# controller-2.net
KiCad netlist of a schematic drawn in EAGLE
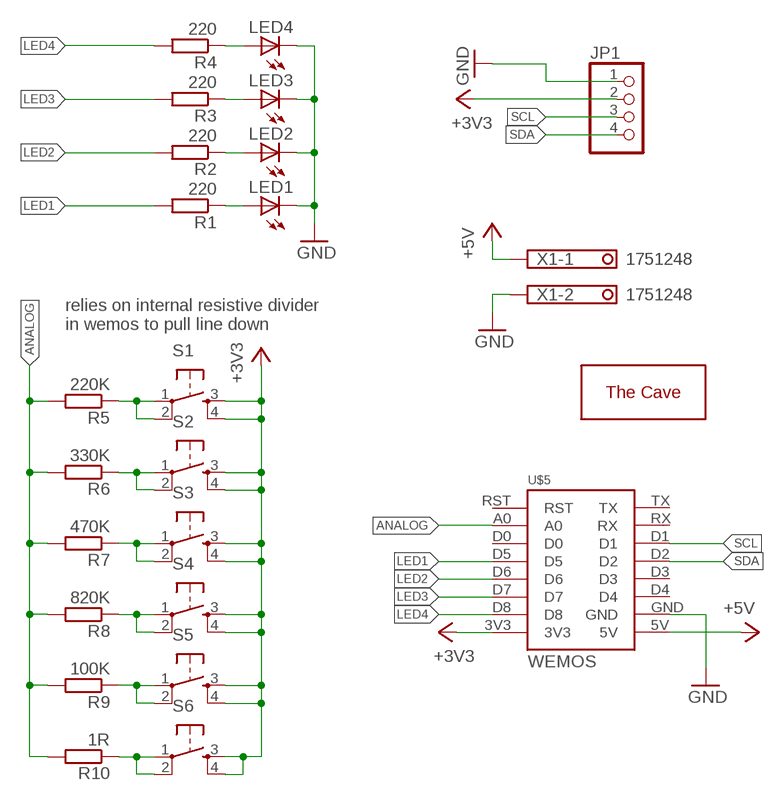
[diagram p0: schematic, sheet 1]

(export (version "E")
  (design (tool "Eeschema 10.0.6"))
  (components
    (comp (ref "JP1")
      (value "PINHD-1X4")
      (footprint "eagle-import:1X04")
      (libsource (lib "eagle-import") (part "PINHD-1X4"))
    )
    (comp (ref "LED1")
      (value "LED5MM")
      (footprint "eagle-import:LED5MM")
      (libsource (lib "eagle-import") (part "LED5MM"))
    )
    (comp (ref "LED2")
      (value "LED5MM")
      (footprint "eagle-import:LED5MM")
      (libsource (lib "eagle-import") (part "LED5MM"))
    )
    (comp (ref "LED3")
      (value "LED5MM")
      (footprint "eagle-import:LED5MM")
      (libsource (lib "eagle-import") (part "LED5MM"))
    )
    (comp (ref "LED4")
      (value "LED5MM")
      (footprint "eagle-import:LED5MM")
      (libsource (lib "eagle-import") (part "LED5MM"))
    )
    (comp (ref "R1")
      (value "220")
      (footprint "eagle-import:R0805")
      (libsource (lib "eagle-import") (part "R-EU_R0805"))
    )
    (comp (ref "R2")
      (value "220")
      (footprint "eagle-import:R0805")
      (libsource (lib "eagle-import") (part "R-EU_R0805"))
    )
    (comp (ref "R3")
      (value "220")
      (footprint "eagle-import:R0805")
      (libsource (lib "eagle-import") (part "R-EU_R0805"))
    )
    (comp (ref "R4")
      (value "220")
      (footprint "eagle-import:R0805")
      (libsource (lib "eagle-import") (part "R-EU_R0805"))
    )
    (comp (ref "R5")
      (value "220K")
      (footprint "eagle-import:R0805")
      (libsource (lib "eagle-import") (part "R-EU_R0805"))
    )
    (comp (ref "R6")
      (value "330K")
      (footprint "eagle-import:R0805")
      (libsource (lib "eagle-import") (part "R-EU_R0805"))
    )
    (comp (ref "R7")
      (value "470K")
      (footprint "eagle-import:R0805")
      (libsource (lib "eagle-import") (part "R-EU_R0805"))
    )
    (comp (ref "R8")
      (value "820K")
      (footprint "eagle-import:R0805")
      (libsource (lib "eagle-import") (part "R-EU_R0805"))
    )
    (comp (ref "R9")
      (value "100K")
      (footprint "eagle-import:R0805")
      (libsource (lib "eagle-import") (part "R-EU_R0805"))
    )
    (comp (ref "R10")
      (value "1R")
      (footprint "eagle-import:R0805")
      (libsource (lib "eagle-import") (part "R-EU_R0805"))
    )
    (comp (ref "S1")
      (value "TACT-SWITCH-6MM-THT")
      (footprint "eagle-import:TACT-SWITCH-6MM-THT")
      (libsource (lib "eagle-import") (part "TACT-SWITCH-6MM-THT"))
    )
    (comp (ref "S2")
      (value "TACT-SWITCH-6MM-THT")
      (footprint "eagle-import:TACT-SWITCH-6MM-THT")
      (libsource (lib "eagle-import") (part "TACT-SWITCH-6MM-THT"))
    )
    (comp (ref "S3")
      (value "TACT-SWITCH-6MM-THT")
      (footprint "eagle-import:TACT-SWITCH-6MM-THT")
      (libsource (lib "eagle-import") (part "TACT-SWITCH-6MM-THT"))
    )
    (comp (ref "S4")
      (value "TACT-SWITCH-6MM-THT")
      (footprint "eagle-import:TACT-SWITCH-6MM-THT")
      (libsource (lib "eagle-import") (part "TACT-SWITCH-6MM-THT"))
    )
    (comp (ref "S5")
      (value "TACT-SWITCH-6MM-THT")
      (footprint "eagle-import:TACT-SWITCH-6MM-THT")
      (libsource (lib "eagle-import") (part "TACT-SWITCH-6MM-THT"))
    )
    (comp (ref "S6")
      (value "TACT-SWITCH-6MM-THT")
      (footprint "eagle-import:TACT-SWITCH-6MM-THT")
      (libsource (lib "eagle-import") (part "TACT-SWITCH-6MM-THT"))
    )
    (comp (ref "U$1")
      (value "THECAVE_LOGO_NEW_TOP_SMALL")
      (footprint "eagle-import:NEW_LOGO_SMALL_TOP")
      (libsource (lib "eagle-import") (part "THECAVE_LOGO_NEW_TOP_SMALL"))
    )
    (comp (ref "U$5")
      (value "WEMOS")
      (footprint "eagle-import:WEMOS")
      (libsource (lib "eagle-import") (part "WEMOS"))
    )
    (comp (ref "X1")
      (value "1751248")
      (footprint "eagle-import:1751248")
      (libsource (lib "eagle-import") (part "1751248"))
    )
  )
  (nets
    (net (code "1") (name "+3V3") (class "Default")
      (node (ref "JP1") (pin "2") (pinfunction "2_2") (pintype "passive"))
      (node (ref "S1") (pin "3") (pinfunction "3_3") (pintype "passive"))
      (node (ref "S1") (pin "4") (pinfunction "4_4") (pintype "passive"))
      (node (ref "S2") (pin "3") (pinfunction "3_3") (pintype "passive"))
      (node (ref "S2") (pin "4") (pinfunction "4_4") (pintype "passive"))
      (node (ref "S3") (pin "3") (pinfunction "3_3") (pintype "passive"))
      (node (ref "S3") (pin "4") (pinfunction "4_4") (pintype "passive"))
      (node (ref "S4") (pin "3") (pinfunction "3_3") (pintype "passive"))
      (node (ref "S4") (pin "4") (pinfunction "4_4") (pintype "passive"))
      (node (ref "S5") (pin "3") (pinfunction "3_3") (pintype "passive"))
      (node (ref "S5") (pin "4") (pinfunction "4_4") (pintype "passive"))
      (node (ref "S6") (pin "3") (pinfunction "3_3") (pintype "passive"))
      (node (ref "S6") (pin "4") (pinfunction "4_4") (pintype "passive"))
      (node (ref "U$5") (pin "3V3") (pinfunction "3V3_3V3") (pintype "bidirectional"))
    )
    (net (code "2") (name "+5V") (class "Default")
      (node (ref "U$5") (pin "5V") (pinfunction "5V_5V") (pintype "bidirectional"))
      (node (ref "X1") (pin "1") (pinfunction "K_1") (pintype "passive"))
    )
    (net (code "3") (name "ANALOG") (class "Default")
      (node (ref "R10") (pin "2") (pinfunction "2_2") (pintype "passive"))
      (node (ref "R5") (pin "2") (pinfunction "2_2") (pintype "passive"))
      (node (ref "R6") (pin "2") (pinfunction "2_2") (pintype "passive"))
      (node (ref "R7") (pin "2") (pinfunction "2_2") (pintype "passive"))
      (node (ref "R8") (pin "2") (pinfunction "2_2") (pintype "passive"))
      (node (ref "R9") (pin "2") (pinfunction "2_2") (pintype "passive"))
      (node (ref "U$5") (pin "A0") (pinfunction "A0_A0") (pintype "bidirectional"))
    )
    (net (code "4") (name "GND") (class "Default")
      (node (ref "JP1") (pin "1") (pinfunction "1_1") (pintype "passive"))
      (node (ref "LED1") (pin "K") (pinfunction "C_K") (pintype "passive"))
      (node (ref "LED2") (pin "K") (pinfunction "C_K") (pintype "passive"))
      (node (ref "LED3") (pin "K") (pinfunction "C_K") (pintype "passive"))
      (node (ref "LED4") (pin "K") (pinfunction "C_K") (pintype "passive"))
      (node (ref "U$5") (pin "GND") (pinfunction "GND_GND") (pintype "bidirectional"))
      (node (ref "X1") (pin "2") (pinfunction "K_2") (pintype "passive"))
    )
    (net (code "5") (name "LED1") (class "Default")
      (node (ref "R1") (pin "2") (pinfunction "2_2") (pintype "passive"))
      (node (ref "U$5") (pin "D5") (pinfunction "D5_D5") (pintype "bidirectional"))
    )
    (net (code "6") (name "LED2") (class "Default")
      (node (ref "R2") (pin "2") (pinfunction "2_2") (pintype "passive"))
      (node (ref "U$5") (pin "D6") (pinfunction "D6_D6") (pintype "bidirectional"))
    )
    (net (code "7") (name "LED3") (class "Default")
      (node (ref "R3") (pin "2") (pinfunction "2_2") (pintype "passive"))
      (node (ref "U$5") (pin "D7") (pinfunction "D7_D7") (pintype "bidirectional"))
    )
    (net (code "8") (name "LED4") (class "Default")
      (node (ref "R4") (pin "2") (pinfunction "2_2") (pintype "passive"))
      (node (ref "U$5") (pin "D8") (pinfunction "D8_D8") (pintype "bidirectional"))
    )
    (net (code "9") (name "Net-(LED1-PadA)") (class "Default")
      (node (ref "LED1") (pin "A") (pinfunction "A_A") (pintype "passive"))
      (node (ref "R1") (pin "1") (pinfunction "1_1") (pintype "passive"))
    )
    (net (code "10") (name "Net-(LED2-PadA)") (class "Default")
      (node (ref "LED2") (pin "A") (pinfunction "A_A") (pintype "passive"))
      (node (ref "R2") (pin "1") (pinfunction "1_1") (pintype "passive"))
    )
    (net (code "11") (name "Net-(LED3-PadA)") (class "Default")
      (node (ref "LED3") (pin "A") (pinfunction "A_A") (pintype "passive"))
      (node (ref "R3") (pin "1") (pinfunction "1_1") (pintype "passive"))
    )
    (net (code "12") (name "Net-(LED4-PadA)") (class "Default")
      (node (ref "LED4") (pin "A") (pinfunction "A_A") (pintype "passive"))
      (node (ref "R4") (pin "1") (pinfunction "1_1") (pintype "passive"))
    )
    (net (code "13") (name "Net-(R5-Pad1)") (class "Default")
      (node (ref "R5") (pin "1") (pinfunction "1_1") (pintype "passive"))
      (node (ref "S1") (pin "1") (pinfunction "1_1") (pintype "passive"))
      (node (ref "S1") (pin "2") (pinfunction "2_2") (pintype "passive"))
    )
    (net (code "14") (name "Net-(R6-Pad1)") (class "Default")
      (node (ref "R6") (pin "1") (pinfunction "1_1") (pintype "passive"))
      (node (ref "S2") (pin "1") (pinfunction "1_1") (pintype "passive"))
      (node (ref "S2") (pin "2") (pinfunction "2_2") (pintype "passive"))
    )
    (net (code "15") (name "Net-(R7-Pad1)") (class "Default")
      (node (ref "R7") (pin "1") (pinfunction "1_1") (pintype "passive"))
      (node (ref "S3") (pin "1") (pinfunction "1_1") (pintype "passive"))
      (node (ref "S3") (pin "2") (pinfunction "2_2") (pintype "passive"))
    )
    (net (code "16") (name "Net-(R8-Pad1)") (class "Default")
      (node (ref "R8") (pin "1") (pinfunction "1_1") (pintype "passive"))
      (node (ref "S4") (pin "1") (pinfunction "1_1") (pintype "passive"))
      (node (ref "S4") (pin "2") (pinfunction "2_2") (pintype "passive"))
    )
    (net (code "17") (name "Net-(R9-Pad1)") (class "Default")
      (node (ref "R9") (pin "1") (pinfunction "1_1") (pintype "passive"))
      (node (ref "S5") (pin "1") (pinfunction "1_1") (pintype "passive"))
      (node (ref "S5") (pin "2") (pinfunction "2_2") (pintype "passive"))
    )
    (net (code "18") (name "Net-(R10-Pad1)") (class "Default")
      (node (ref "R10") (pin "1") (pinfunction "1_1") (pintype "passive"))
      (node (ref "S6") (pin "1") (pinfunction "1_1") (pintype "passive"))
      (node (ref "S6") (pin "2") (pinfunction "2_2") (pintype "passive"))
    )
    (net (code "19") (name "SCL") (class "Default")
      (node (ref "JP1") (pin "3") (pinfunction "3_3") (pintype "passive"))
      (node (ref "U$5") (pin "D1") (pinfunction "D1_D1") (pintype "bidirectional"))
    )
    (net (code "20") (name "SDA") (class "Default")
      (node (ref "JP1") (pin "4") (pinfunction "4_4") (pintype "passive"))
      (node (ref "U$5") (pin "D2") (pinfunction "D2_D2") (pintype "bidirectional"))
    )
    (net (code "21") (name "unconnected-(U$5-PadD0)") (class "Default")
      (node (ref "U$5") (pin "D0") (pinfunction "D0_D0") (pintype "bidirectional"))
    )
    (net (code "22") (name "unconnected-(U$5-PadD3)") (class "Default")
      (node (ref "U$5") (pin "D3") (pinfunction "D3_D3") (pintype "bidirectional"))
    )
    (net (code "23") (name "unconnected-(U$5-PadD4)") (class "Default")
      (node (ref "U$5") (pin "D4") (pinfunction "D4_D4") (pintype "bidirectional"))
    )
    (net (code "24") (name "unconnected-(U$5-PadRST)") (class "Default")
      (node (ref "U$5") (pin "RST") (pinfunction "RST_RST") (pintype "bidirectional"))
    )
    (net (code "25") (name "unconnected-(U$5-PadRX)") (class "Default")
      (node (ref "U$5") (pin "RX") (pinfunction "RX_RX") (pintype "bidirectional"))
    )
    (net (code "26") (name "unconnected-(U$5-PadTX)") (class "Default")
      (node (ref "U$5") (pin "TX") (pinfunction "TX_TX") (pintype "bidirectional"))
    )
  )
)
